# Power.net
KiCad netlist of a schematic drawn in Altium Designer
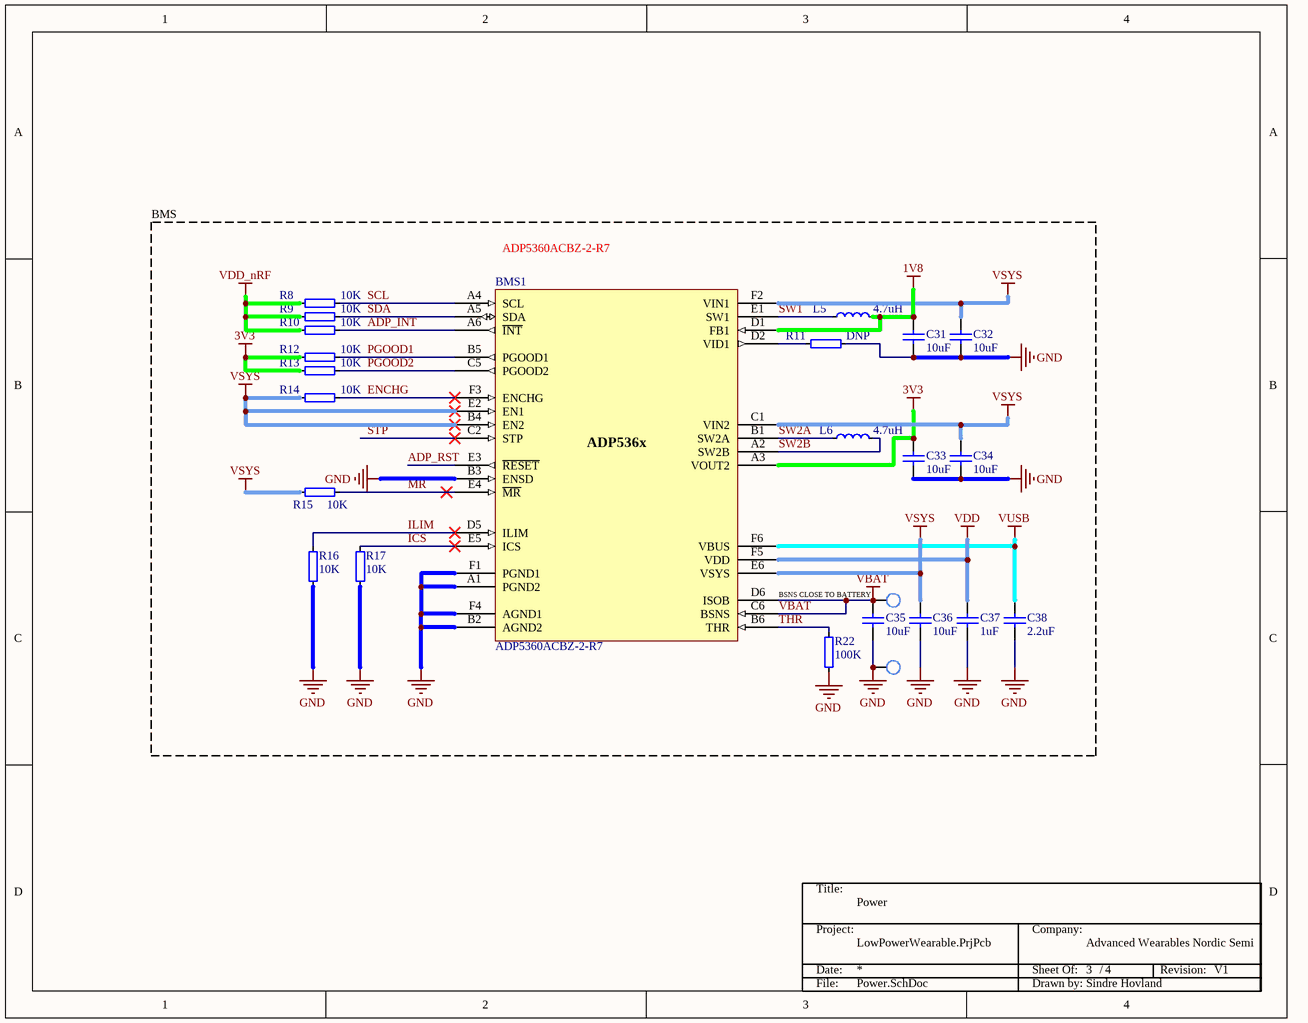
[diagram p0: Power.SchDoc]

(export (version "E")
  (design (tool "Eeschema 10.0.6"))
  (components
    (comp (ref "BMS1")
      (value "ADP5360ACBZ-2-R7")
      (footprint "BGA32C40P6X6_238X238X56")
      (description "Advanced Battery Management PMIC With Ultralow Iq Buck and Buck-Boost. Order: ADP5360ACBZ-2-R7")
      (fields
        (field (name "PART NUMBER") "ADP536x")
        (field (name "MANUFACTURER") "Analog Devices")
        (field (name "PUBLISHER") "Nordic Semiconductor")
      )
      (libsource (lib "NeuronV4") (part "ADP536x"))
    )
    (comp (ref "C31")
      (value "10uF")
      (footprint "C0603")
      (description "Capacitor")
      (fields (field (name "PUBLISHER") "Altium Limited"))
      (libsource (lib "NeuronV4") (part "CAP"))
    )
    (comp (ref "C32")
      (value "10uF")
      (footprint "C0603")
      (description "Capacitor")
      (fields (field (name "PUBLISHER") "Altium Limited"))
      (libsource (lib "NeuronV4") (part "CAP"))
    )
    (comp (ref "C33")
      (value "10uF")
      (footprint "C0603")
      (description "Capacitor")
      (fields (field (name "PUBLISHER") "Altium Limited"))
      (libsource (lib "NeuronV4") (part "CAP"))
    )
    (comp (ref "C34")
      (value "10uF")
      (footprint "C0603")
      (description "Capacitor")
      (fields (field (name "PUBLISHER") "Altium Limited"))
      (libsource (lib "NeuronV4") (part "CAP"))
    )
    (comp (ref "C35")
      (value "10uF")
      (footprint "C0603")
      (description "Capacitor")
      (fields (field (name "PUBLISHER") "Altium Limited"))
      (libsource (lib "NeuronV4") (part "CAP"))
    )
    (comp (ref "C36")
      (value "10uF")
      (footprint "C0603")
      (description "Capacitor")
      (fields (field (name "PUBLISHER") "Altium Limited"))
      (libsource (lib "NeuronV4") (part "CAP"))
    )
    (comp (ref "C37")
      (value "1uF")
      (footprint "C0402")
      (description "Capacitor")
      (fields (field (name "PUBLISHER") "Altium Limited"))
      (libsource (lib "NeuronV4") (part "CAP"))
    )
    (comp (ref "C38")
      (value "2.2uF")
      (footprint "C0402")
      (description "Capacitor")
      (fields (field (name "PUBLISHER") "Altium Limited"))
      (libsource (lib "NeuronV4") (part "CAP"))
    )
    (comp (ref "GND") (value "DNP") (footprint "TP_SMD_1.0mm") (libsource (lib "MISC") (part "TP")))
    (comp (ref "L5")
      (value "4.7uH")
      (footprint "IND2016")
      (description "Inductor")
      (fields
        (field (name "PART NUMBER") "FB0402-120R@100M-500mA")
        (field (name "MANUFACTURER") "Murata")
        (field (name "PUBLISHER") "Nordic Semiconductor")
      )
      (libsource (lib "NeuronV4") (part "IND"))
    )
    (comp (ref "L6")
      (value "4.7uH")
      (footprint "IND2016")
      (description "Inductor")
      (fields
        (field (name "PART NUMBER") "FB0402-120R@100M-500mA")
        (field (name "MANUFACTURER") "Murata")
        (field (name "PUBLISHER") "Nordic Semiconductor")
      )
      (libsource (lib "NeuronV4") (part "IND"))
    )
    (comp (ref "R8")
      (value "10K")
      (footprint "RES0402")
      (description "Resistor, ±5%, 0.05W")
      (fields (field (name "PART NUMBER") "R0201-0R") (field (name "PUBLISHER") "Nordic Semiconductor"))
      (libsource (lib "NeuronV4") (part "RES"))
    )
    (comp (ref "R9")
      (value "10K")
      (footprint "RES0402")
      (description "Resistor, ±5%, 0.05W")
      (fields (field (name "PART NUMBER") "R0201-0R") (field (name "PUBLISHER") "Nordic Semiconductor"))
      (libsource (lib "NeuronV4") (part "RES"))
    )
    (comp (ref "R10")
      (value "10K")
      (footprint "RES0402")
      (description "Resistor, ±5%, 0.05W")
      (fields (field (name "PART NUMBER") "R0201-0R") (field (name "PUBLISHER") "Nordic Semiconductor"))
      (libsource (lib "NeuronV4") (part "RES"))
    )
    (comp (ref "R11")
      (value "DNP")
      (footprint "RES0402")
      (description "Resistor, ±5%, 0.05W")
      (fields (field (name "PART NUMBER") "R0201-0R") (field (name "PUBLISHER") "Nordic Semiconductor"))
      (libsource (lib "NeuronV4") (part "RES"))
    )
    (comp (ref "R12")
      (value "10K")
      (footprint "RES0402")
      (description "Resistor, ±5%, 0.05W")
      (fields (field (name "PART NUMBER") "R0201-0R") (field (name "PUBLISHER") "Nordic Semiconductor"))
      (libsource (lib "NeuronV4") (part "RES"))
    )
    (comp (ref "R13")
      (value "10K")
      (footprint "RES0402")
      (description "Resistor, ±5%, 0.05W")
      (fields (field (name "PART NUMBER") "R0201-0R") (field (name "PUBLISHER") "Nordic Semiconductor"))
      (libsource (lib "NeuronV4") (part "RES"))
    )
    (comp (ref "R14")
      (value "10K")
      (footprint "RES0402")
      (description "Resistor, ±5%, 0.05W")
      (fields (field (name "PART NUMBER") "R0201-0R") (field (name "PUBLISHER") "Nordic Semiconductor"))
      (libsource (lib "NeuronV4") (part "RES"))
    )
    (comp (ref "R15")
      (value "10K")
      (footprint "RES0402")
      (description "Resistor, ±5%, 0.05W")
      (fields (field (name "PART NUMBER") "R0201-0R") (field (name "PUBLISHER") "Nordic Semiconductor"))
      (libsource (lib "NeuronV4") (part "RES"))
    )
    (comp (ref "R16")
      (value "10K")
      (footprint "RES0402")
      (description "Resistor, ±5%, 0.05W")
      (fields (field (name "PART NUMBER") "R0201-0R") (field (name "PUBLISHER") "Nordic Semiconductor"))
      (libsource (lib "NeuronV4") (part "RES"))
    )
    (comp (ref "R17")
      (value "10K")
      (footprint "RES0402")
      (description "Resistor, ±5%, 0.05W")
      (fields (field (name "PART NUMBER") "R0201-0R") (field (name "PUBLISHER") "Nordic Semiconductor"))
      (libsource (lib "NeuronV4") (part "RES"))
    )
    (comp (ref "R22")
      (value "100K")
      (footprint "RES0402")
      (description "Resistor, ±5%, 0.05W")
      (fields (field (name "PART NUMBER") "R0201-0R") (field (name "PUBLISHER") "Nordic Semiconductor"))
      (libsource (lib "NeuronV4") (part "RES"))
    )
    (comp (ref "VBAT") (value "DNP") (footprint "TP_SMD_1.0mm") (libsource (lib "MISC") (part "TP")))
  )
  (nets
    (net (code "1") (name "/ADP_INT") (class "Default")
      (node (ref "BMS1") (pin "A6") (pinfunction "~{INT}_A6") (pintype "output"))
      (node (ref "R10") (pin "2") (pinfunction "2_2") (pintype "passive"))
    )
    (net (code "2") (name "/ADP_RST") (class "Default")
      (node (ref "BMS1") (pin "E3") (pinfunction "~{RESET}_E3") (pintype "output"))
    )
    (net (code "3") (name "/ENCHG") (class "Default")
      (node (ref "BMS1") (pin "F3") (pinfunction "ENCHG_F3") (pintype "input"))
      (node (ref "R14") (pin "2") (pinfunction "2_2") (pintype "passive"))
    )
    (net (code "4") (name "/ICS") (class "Default")
      (node (ref "BMS1") (pin "E5") (pinfunction "ICS_E5") (pintype "input"))
      (node (ref "R17") (pin "1") (pinfunction "1_1") (pintype "passive"))
    )
    (net (code "5") (name "/ILIM") (class "Default")
      (node (ref "BMS1") (pin "D5") (pinfunction "ILIM_D5") (pintype "input"))
      (node (ref "R16") (pin "1") (pinfunction "1_1") (pintype "passive"))
    )
    (net (code "6") (name "/PGOOD1") (class "Default")
      (node (ref "BMS1") (pin "B5") (pinfunction "PGOOD1_B5") (pintype "output"))
      (node (ref "R12") (pin "2") (pinfunction "2_2") (pintype "passive"))
    )
    (net (code "7") (name "/PGOOD2") (class "Default")
      (node (ref "BMS1") (pin "C5") (pinfunction "PGOOD2_C5") (pintype "output"))
      (node (ref "R13") (pin "2") (pinfunction "2_2") (pintype "passive"))
    )
    (net (code "8") (name "/SCL") (class "Default")
      (node (ref "BMS1") (pin "A4") (pinfunction "SCL_A4") (pintype "input"))
      (node (ref "R8") (pin "2") (pinfunction "2_2") (pintype "passive"))
    )
    (net (code "9") (name "/SDA") (class "Default")
      (node (ref "BMS1") (pin "A5") (pinfunction "SDA_A5") (pintype "bidirectional"))
      (node (ref "R9") (pin "2") (pinfunction "2_2") (pintype "passive"))
    )
    (net (code "10") (name "/STP") (class "Default")
      (node (ref "BMS1") (pin "C2") (pinfunction "STP_C2") (pintype "input+no_connect"))
    )
    (net (code "11") (name "/SW1") (class "Default")
      (node (ref "BMS1") (pin "E1") (pinfunction "SW1_E1") (pintype "power_in"))
      (node (ref "L5") (pin "1") (pinfunction "1_1") (pintype "passive"))
    )
    (net (code "12") (name "/SW2A") (class "Default")
      (node (ref "BMS1") (pin "B1") (pinfunction "SW2A_B1") (pintype "power_in"))
      (node (ref "L6") (pin "1") (pinfunction "1_1") (pintype "passive"))
    )
    (net (code "13") (name "/SW2B") (class "Default")
      (node (ref "BMS1") (pin "A2") (pinfunction "SW2B_A2") (pintype "power_in"))
      (node (ref "L6") (pin "2") (pinfunction "2_2") (pintype "passive"))
    )
    (net (code "14") (name "/THR") (class "Default")
      (node (ref "BMS1") (pin "B6") (pinfunction "THR_B6") (pintype "input"))
      (node (ref "R22") (pin "1") (pinfunction "1_1") (pintype "passive"))
    )
    (net (code "15") (name "/~{MR}") (class "Default")
      (node (ref "BMS1") (pin "E4") (pinfunction "~{MR}_E4") (pintype "input"))
      (node (ref "R15") (pin "2") (pinfunction "2_2") (pintype "passive"))
    )
    (net (code "16") (name "1V8") (class "Default")
      (node (ref "BMS1") (pin "D1") (pinfunction "FB1_D1") (pintype "input"))
      (node (ref "C31") (pin "2") (pinfunction "2_2") (pintype "passive"))
      (node (ref "L5") (pin "2") (pinfunction "2_2") (pintype "passive"))
    )
    (net (code "17") (name "3V3") (class "Default")
      (node (ref "BMS1") (pin "A3") (pinfunction "VOUT2_A3") (pintype "power_in"))
      (node (ref "C33") (pin "2") (pinfunction "2_2") (pintype "passive"))
      (node (ref "R12") (pin "1") (pinfunction "1_1") (pintype "passive"))
      (node (ref "R13") (pin "1") (pinfunction "1_1") (pintype "passive"))
    )
    (net (code "18") (name "GND") (class "Default")
      (node (ref "BMS1") (pin "A1") (pinfunction "PGND2_A1") (pintype "power_in"))
      (node (ref "BMS1") (pin "B2") (pinfunction "AGND2_B2") (pintype "power_in"))
      (node (ref "BMS1") (pin "B3") (pinfunction "ENSD_B3") (pintype "input"))
      (node (ref "BMS1") (pin "F1") (pinfunction "PGND1_F1") (pintype "power_in"))
      (node (ref "BMS1") (pin "F4") (pinfunction "AGND1_F4") (pintype "power_in"))
      (node (ref "C31") (pin "1") (pinfunction "1_1") (pintype "passive"))
      (node (ref "C32") (pin "1") (pinfunction "1_1") (pintype "passive"))
      (node (ref "C33") (pin "1") (pinfunction "1_1") (pintype "passive"))
      (node (ref "C34") (pin "1") (pinfunction "1_1") (pintype "passive"))
      (node (ref "C35") (pin "1") (pinfunction "1_1") (pintype "passive"))
      (node (ref "C36") (pin "1") (pinfunction "1_1") (pintype "passive"))
      (node (ref "C37") (pin "1") (pinfunction "1_1") (pintype "passive"))
      (node (ref "C38") (pin "1") (pinfunction "1_1") (pintype "passive"))
      (node (ref "GND") (pin "1") (pinfunction "1_1") (pintype "passive"))
      (node (ref "R11") (pin "2") (pinfunction "2_2") (pintype "passive"))
      (node (ref "R16") (pin "2") (pinfunction "2_2") (pintype "passive"))
      (node (ref "R17") (pin "2") (pinfunction "2_2") (pintype "passive"))
      (node (ref "R22") (pin "2") (pinfunction "2_2") (pintype "passive"))
    )
    (net (code "19") (name "Net-(BMS1-VID1)") (class "Default")
      (node (ref "BMS1") (pin "D2") (pinfunction "VID1_D2") (pintype "output"))
      (node (ref "R11") (pin "1") (pinfunction "1_1") (pintype "passive"))
    )
    (net (code "20") (name "VBAT") (class "Default")
      (node (ref "BMS1") (pin "C6") (pinfunction "BSNS_C6") (pintype "input"))
      (node (ref "BMS1") (pin "D6") (pinfunction "ISOB_D6") (pintype "power_in"))
      (node (ref "C35") (pin "2") (pinfunction "2_2") (pintype "passive"))
      (node (ref "VBAT") (pin "1") (pinfunction "1_1") (pintype "passive"))
    )
    (net (code "21") (name "VDD") (class "Default")
      (node (ref "BMS1") (pin "F5") (pinfunction "VDD_F5") (pintype "power_in"))
      (node (ref "C37") (pin "2") (pinfunction "2_2") (pintype "passive"))
    )
    (net (code "22") (name "VDD_nRF") (class "Default")
      (node (ref "R10") (pin "1") (pinfunction "1_1") (pintype "passive"))
      (node (ref "R8") (pin "1") (pinfunction "1_1") (pintype "passive"))
      (node (ref "R9") (pin "1") (pinfunction "1_1") (pintype "passive"))
    )
    (net (code "23") (name "VSYS") (class "Default")
      (node (ref "BMS1") (pin "B4") (pinfunction "EN2_B4") (pintype "input"))
      (node (ref "BMS1") (pin "C1") (pinfunction "VIN2_C1") (pintype "power_in"))
      (node (ref "BMS1") (pin "E2") (pinfunction "EN1_E2") (pintype "input"))
      (node (ref "BMS1") (pin "E6") (pinfunction "VSYS_E6") (pintype "power_in"))
      (node (ref "BMS1") (pin "F2") (pinfunction "VIN1_F2") (pintype "power_in"))
      (node (ref "C32") (pin "2") (pinfunction "2_2") (pintype "passive"))
      (node (ref "C34") (pin "2") (pinfunction "2_2") (pintype "passive"))
      (node (ref "C36") (pin "2") (pinfunction "2_2") (pintype "passive"))
      (node (ref "R14") (pin "1") (pinfunction "1_1") (pintype "passive"))
      (node (ref "R15") (pin "1") (pinfunction "1_1") (pintype "passive"))
    )
    (net (code "24") (name "VUSB") (class "Default")
      (node (ref "BMS1") (pin "F6") (pinfunction "VBUS_F6") (pintype "power_in"))
      (node (ref "C38") (pin "2") (pinfunction "2_2") (pintype "passive"))
    )
  )
)
